# OpenBook.net
KiCad netlist of a schematic drawn in EAGLE
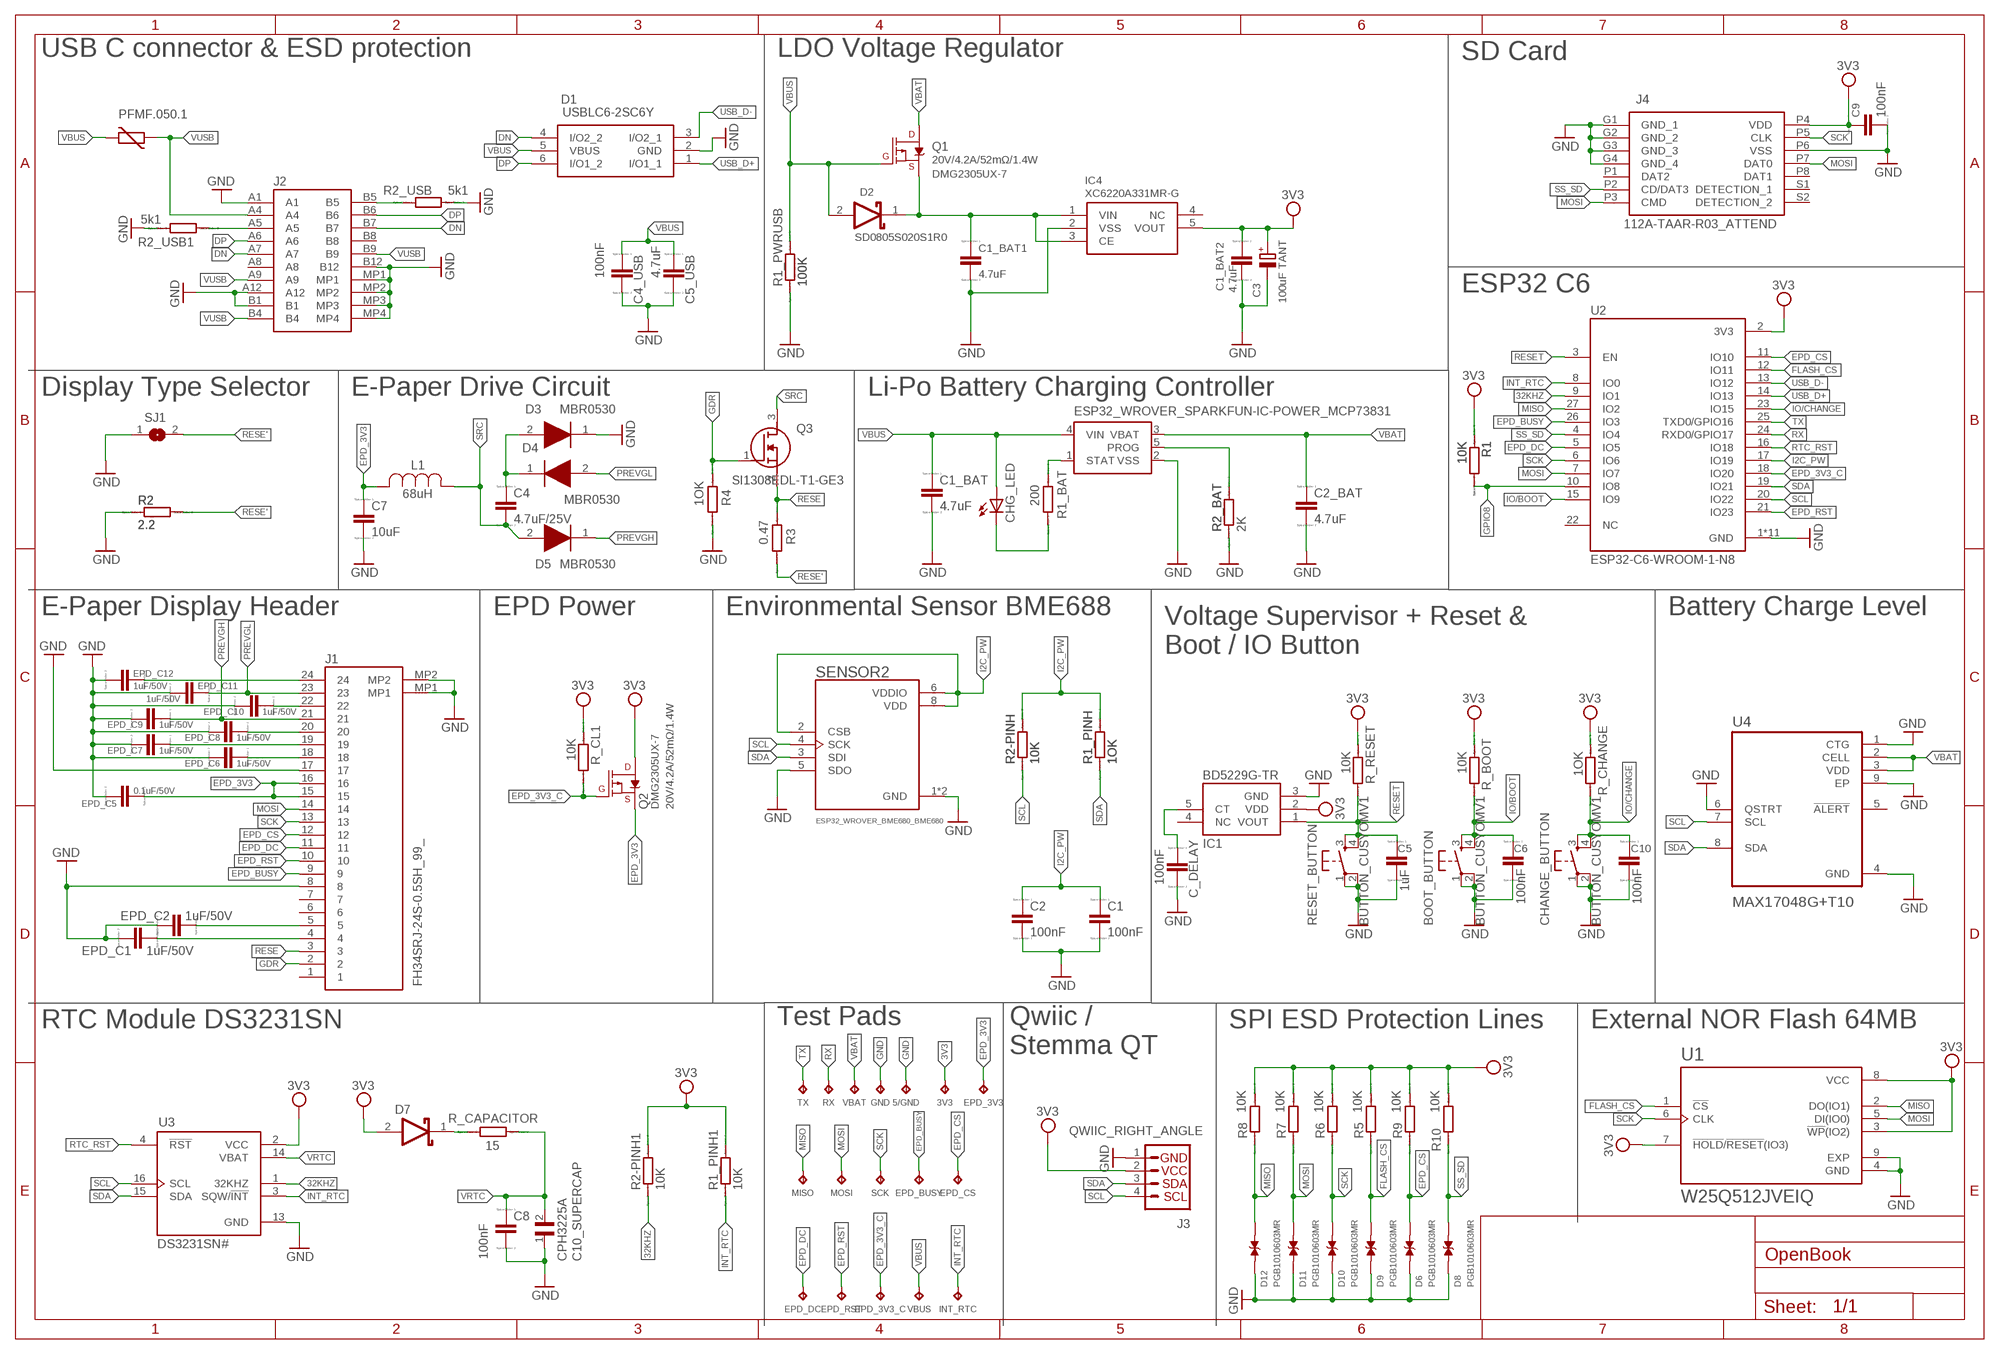
[diagram p0: schematic, sheet 1]

(export (version "E")
  (design (tool "Eeschema 10.0.6"))
  (components
    (comp (ref "3V3")
      (value "TPTP20R")
      (footprint "eagle-import:TP20R")
      (libsource (lib "eagle-import") (part "TPTP20R"))
    )
    (comp (ref "5/GND")
      (value "TPTP20R")
      (footprint "eagle-import:TP20R")
      (libsource (lib "eagle-import") (part "TPTP20R"))
    )
    (comp (ref "BOOT_BUTTON")
      (value "BUTTON_CUSYOMV1")
      (footprint "eagle-import:MYBUTTON")
      (libsource (lib "eagle-import") (part "BUTTON_CUSYOMV1"))
    )
    (comp (ref "C1")
      (value "100nF")
      (footprint "eagle-import:ESP32_WROVER_EAGLE-LTSPICE_C0402")
      (libsource (lib "eagle-import") (part "ESP32_WROVER_EAGLE-LTSPICE_CC0402"))
    )
    (comp (ref "C1_BAT")
      (value "4.7uF")
      (footprint "eagle-import:ESP32_WROVER_EAGLE-LTSPICE_C0402")
      (libsource (lib "eagle-import") (part "ESP32_WROVER_EAGLE-LTSPICE_CC0402"))
    )
    (comp (ref "C1_BAT1")
      (value "4.7uF")
      (footprint "eagle-import:ESP32_WROVER_EAGLE-LTSPICE_C0402")
      (libsource (lib "eagle-import") (part "ESP32_WROVER_EAGLE-LTSPICE_CC0402"))
    )
    (comp (ref "C1_BAT2")
      (value "4.7uF")
      (footprint "eagle-import:ESP32_WROVER_EAGLE-LTSPICE_C0402")
      (libsource (lib "eagle-import") (part "ESP32_WROVER_EAGLE-LTSPICE_CC0402"))
    )
    (comp (ref "C2")
      (value "100nF")
      (footprint "eagle-import:ESP32_WROVER_EAGLE-LTSPICE_C0402")
      (libsource (lib "eagle-import") (part "ESP32_WROVER_EAGLE-LTSPICE_CC0402"))
    )
    (comp (ref "C2_BAT")
      (value "4.7uF")
      (footprint "eagle-import:ESP32_WROVER_EAGLE-LTSPICE_C0402")
      (libsource (lib "eagle-import") (part "ESP32_WROVER_EAGLE-LTSPICE_CC0402"))
    )
    (comp (ref "C3")
      (value "100uF TANT")
      (footprint "eagle-import:RCL_CT3528")
      (libsource (lib "eagle-import") (part "RCL_CPOL-EUCT3528"))
    )
    (comp (ref "C4")
      (value "4.7uF/25V")
      (footprint "eagle-import:ESP32_WROVER_EAGLE-LTSPICE_C0402")
      (libsource (lib "eagle-import") (part "ESP32_WROVER_EAGLE-LTSPICE_CC0402"))
    )
    (comp (ref "C4_USB")
      (value "100nF")
      (footprint "eagle-import:ESP32_WROVER_EAGLE-LTSPICE_C0402")
      (libsource (lib "eagle-import") (part "ESP32_WROVER_EAGLE-LTSPICE_CC0402"))
    )
    (comp (ref "C5")
      (value "1uF")
      (footprint "eagle-import:ESP32_WROVER_EAGLE-LTSPICE_C0402")
      (libsource (lib "eagle-import") (part "ESP32_WROVER_EAGLE-LTSPICE_CC0402"))
    )
    (comp (ref "C5_USB")
      (value "4.7uF")
      (footprint "eagle-import:ESP32_WROVER_EAGLE-LTSPICE_C0402")
      (libsource (lib "eagle-import") (part "ESP32_WROVER_EAGLE-LTSPICE_CC0402"))
    )
    (comp (ref "C6")
      (value "100nF")
      (footprint "eagle-import:ESP32_WROVER_EAGLE-LTSPICE_C0402")
      (libsource (lib "eagle-import") (part "ESP32_WROVER_EAGLE-LTSPICE_CC0402"))
    )
    (comp (ref "C7")
      (value "10uF")
      (footprint "eagle-import:ESP32_WROVER_EAGLE-LTSPICE_C0402")
      (libsource (lib "eagle-import") (part "ESP32_WROVER_EAGLE-LTSPICE_CC0402"))
    )
    (comp (ref "C8")
      (value "100nF")
      (footprint "eagle-import:ESP32_WROVER_EAGLE-LTSPICE_C0402")
      (libsource (lib "eagle-import") (part "ESP32_WROVER_EAGLE-LTSPICE_CC0402"))
    )
    (comp (ref "C9")
      (value "100nF")
      (footprint "eagle-import:ESP32_WROVER_EAGLE-LTSPICE_C0402")
      (libsource (lib "eagle-import") (part "ESP32_WROVER_EAGLE-LTSPICE_CC0402"))
    )
    (comp (ref "C10")
      (value "100nF")
      (footprint "eagle-import:ESP32_WROVER_EAGLE-LTSPICE_C0402")
      (libsource (lib "eagle-import") (part "ESP32_WROVER_EAGLE-LTSPICE_CC0402"))
    )
    (comp (ref "C10_SUPERCAP")
      (value "CPH3225A")
      (footprint "eagle-import:CAPCP3225X100N")
      (fields (field (name "MF") "Seiko Instruments"))
      (libsource (lib "eagle-import") (part "CPH3225A"))
    )
    (comp (ref "CHANGE_BUTTON")
      (value "BUTTON_CUSYOMV1")
      (footprint "eagle-import:MYBUTTON")
      (libsource (lib "eagle-import") (part "BUTTON_CUSYOMV1"))
    )
    (comp (ref "CHG_LED")
      (value "ADAFRUIT_LEDCHIP-LED0603")
      (footprint "eagle-import:ADAFRUIT_CHIP-LED0603")
      (libsource (lib "eagle-import") (part "ADAFRUIT_LEDCHIP-LED0603"))
    )
    (comp (ref "C_DELAY")
      (value "100nF")
      (footprint "eagle-import:ESP32_WROVER_EAGLE-LTSPICE_C0402")
      (libsource (lib "eagle-import") (part "ESP32_WROVER_EAGLE-LTSPICE_CC0402"))
    )
    (comp (ref "D1")
      (value "USBLC6-2SC6Y")
      (footprint "eagle-import:SOT95P280X145-6N")
      (fields (field (name "MF") "STMicroelectronics"))
      (libsource (lib "eagle-import") (part "USBLC6-2SC6Y"))
    )
    (comp (ref "D2")
      (value "ESP32_WROVER_AVX---SD0805S020S1R0_AVX_SD0805S020S1R0_0_0AVX_SD0805S020S1R0_0_0")
      (footprint "eagle-import:ESP32_WROVER_AVX---SD0805S020S1R0_AVX_SD0805S020S1R0_0")
      (fields
        (field (name "DIGIKEY_PART_NUMBER") "478-7800-1-ND")
        (field (name "MF") "AVX")
        (field (name "MOUSER_PART_NUMBER") "581-SD0805S020S1R0")
      )
      (libsource (lib "eagle-import") (part "ESP32_WROVER_AVX---SD0805S020S1R0_AVX_SD0805S020S1R0_0_0AVX_SD0805S020S1R0_0_0"))
    )
    (comp (ref "D3")
      (value "MBR0530")
      (footprint "eagle-import:SOD3716X135N")
      (fields (field (name "MF") "ON Semiconductor"))
      (libsource (lib "eagle-import") (part "MBR0530"))
    )
    (comp (ref "D4")
      (value "MBR0530")
      (footprint "eagle-import:SOD3716X135N")
      (fields (field (name "MF") "ON Semiconductor"))
      (libsource (lib "eagle-import") (part "MBR0530"))
    )
    (comp (ref "D5")
      (value "MBR0530")
      (footprint "eagle-import:SOD3716X135N")
      (fields (field (name "MF") "ON Semiconductor"))
      (libsource (lib "eagle-import") (part "MBR0530"))
    )
    (comp (ref "D6")
      (value "PGB1010603MR")
      (footprint "eagle-import:DIOC1608X36N")
      (fields (field (name "MF") "Littelfuse Inc."))
      (libsource (lib "eagle-import") (part "PGB1010603MR"))
    )
    (comp (ref "D7")
      (value "ESP32_WROVER_AVX---SD0805S020S1R0_AVX_SD0805S020S1R0_0_0AVX_SD0805S020S1R0_0_0")
      (footprint "eagle-import:ESP32_WROVER_AVX---SD0805S020S1R0_AVX_SD0805S020S1R0_0")
      (fields
        (field (name "DIGIKEY_PART_NUMBER") "478-7800-1-ND")
        (field (name "MF") "AVX")
        (field (name "MOUSER_PART_NUMBER") "581-SD0805S020S1R0")
      )
      (libsource (lib "eagle-import") (part "ESP32_WROVER_AVX---SD0805S020S1R0_AVX_SD0805S020S1R0_0_0AVX_SD0805S020S1R0_0_0"))
    )
    (comp (ref "D8")
      (value "PGB1010603MR")
      (footprint "eagle-import:DIOC1608X36N")
      (fields (field (name "MF") "Littelfuse Inc."))
      (libsource (lib "eagle-import") (part "PGB1010603MR"))
    )
    (comp (ref "D9")
      (value "PGB1010603MR")
      (footprint "eagle-import:DIOC1608X36N")
      (fields (field (name "MF") "Littelfuse Inc."))
      (libsource (lib "eagle-import") (part "PGB1010603MR"))
    )
    (comp (ref "D10")
      (value "PGB1010603MR")
      (footprint "eagle-import:DIOC1608X36N")
      (fields (field (name "MF") "Littelfuse Inc."))
      (libsource (lib "eagle-import") (part "PGB1010603MR"))
    )
    (comp (ref "D11")
      (value "PGB1010603MR")
      (footprint "eagle-import:DIOC1608X36N")
      (fields (field (name "MF") "Littelfuse Inc."))
      (libsource (lib "eagle-import") (part "PGB1010603MR"))
    )
    (comp (ref "D12")
      (value "PGB1010603MR")
      (footprint "eagle-import:DIOC1608X36N")
      (fields (field (name "MF") "Littelfuse Inc."))
      (libsource (lib "eagle-import") (part "PGB1010603MR"))
    )
    (comp (ref "EPD_3V3")
      (value "TPTP20R")
      (footprint "eagle-import:TP20R")
      (libsource (lib "eagle-import") (part "TPTP20R"))
    )
    (comp (ref "EPD_3V3_C")
      (value "TPTP20R")
      (footprint "eagle-import:TP20R")
      (libsource (lib "eagle-import") (part "TPTP20R"))
    )
    (comp (ref "EPD_BUSY")
      (value "TPTP20R")
      (footprint "eagle-import:TP20R")
      (libsource (lib "eagle-import") (part "TPTP20R"))
    )
    (comp (ref "EPD_C1")
      (value "1uF/50V")
      (footprint "eagle-import:ESP32_WROVER_EAGLE-LTSPICE_C0402")
      (libsource (lib "eagle-import") (part "ESP32_WROVER_EAGLE-LTSPICE_CC0402"))
    )
    (comp (ref "EPD_C2")
      (value "1uF/50V")
      (footprint "eagle-import:ESP32_WROVER_EAGLE-LTSPICE_C0402")
      (libsource (lib "eagle-import") (part "ESP32_WROVER_EAGLE-LTSPICE_CC0402"))
    )
    (comp (ref "EPD_C5")
      (value "0.1uF/50V")
      (footprint "eagle-import:ESP32_WROVER_EAGLE-LTSPICE_C0402")
      (libsource (lib "eagle-import") (part "ESP32_WROVER_EAGLE-LTSPICE_CC0402"))
    )
    (comp (ref "EPD_C6")
      (value "1uF/50V")
      (footprint "eagle-import:ESP32_WROVER_EAGLE-LTSPICE_C0402")
      (libsource (lib "eagle-import") (part "ESP32_WROVER_EAGLE-LTSPICE_CC0402"))
    )
    (comp (ref "EPD_C7")
      (value "1uF/50V")
      (footprint "eagle-import:ESP32_WROVER_EAGLE-LTSPICE_C0402")
      (libsource (lib "eagle-import") (part "ESP32_WROVER_EAGLE-LTSPICE_CC0402"))
    )
    (comp (ref "EPD_C8")
      (value "1uF/50V")
      (footprint "eagle-import:ESP32_WROVER_EAGLE-LTSPICE_C0402")
      (libsource (lib "eagle-import") (part "ESP32_WROVER_EAGLE-LTSPICE_CC0402"))
    )
    (comp (ref "EPD_C9")
      (value "1uF/50V")
      (footprint "eagle-import:ESP32_WROVER_EAGLE-LTSPICE_C0402")
      (libsource (lib "eagle-import") (part "ESP32_WROVER_EAGLE-LTSPICE_CC0402"))
    )
    (comp (ref "EPD_C10")
      (value "1uF/50V")
      (footprint "eagle-import:ESP32_WROVER_EAGLE-LTSPICE_C0402")
      (libsource (lib "eagle-import") (part "ESP32_WROVER_EAGLE-LTSPICE_CC0402"))
    )
    (comp (ref "EPD_C11")
      (value "1uF/50V")
      (footprint "eagle-import:ESP32_WROVER_EAGLE-LTSPICE_C0402")
      (libsource (lib "eagle-import") (part "ESP32_WROVER_EAGLE-LTSPICE_CC0402"))
    )
    (comp (ref "EPD_C12")
      (value "1uF/50V")
      (footprint "eagle-import:ESP32_WROVER_EAGLE-LTSPICE_C0402")
      (libsource (lib "eagle-import") (part "ESP32_WROVER_EAGLE-LTSPICE_CC0402"))
    )
    (comp (ref "EPD_CS")
      (value "TPTP20R")
      (footprint "eagle-import:TP20R")
      (libsource (lib "eagle-import") (part "TPTP20R"))
    )
    (comp (ref "EPD_DC")
      (value "TPTP20R")
      (footprint "eagle-import:TP20R")
      (libsource (lib "eagle-import") (part "TPTP20R"))
    )
    (comp (ref "EPD_RST")
      (value "TPTP20R")
      (footprint "eagle-import:TP20R")
      (libsource (lib "eagle-import") (part "TPTP20R"))
    )
    (comp (ref "GND")
      (value "TPTP20R")
      (footprint "eagle-import:TP20R")
      (libsource (lib "eagle-import") (part "TPTP20R"))
    )
    (comp (ref "IC1")
      (value "BD5229G-TR")
      (footprint "eagle-import:SOT95P280X125-5N")
      (fields (field (name "MOUSER_PART_NUMBER") "755-BD5229G-TR"))
      (libsource (lib "eagle-import") (part "BD5229G-TR"))
    )
    (comp (ref "IC4")
      (value "XC6220A331MR-G")
      (footprint "eagle-import:SOT95P280X120-5N")
      (fields (field (name "MOUSER_PART_NUMBER") "865-XC6220A331MR-G"))
      (libsource (lib "eagle-import") (part "XC6220A331MR-G"))
    )
    (comp (ref "INT_RTC")
      (value "TPTP20R")
      (footprint "eagle-import:TP20R")
      (libsource (lib "eagle-import") (part "TPTP20R"))
    )
    (comp (ref "J1")
      (value "FH34SRJ-24S-0.5SH_99_")
      (footprint "eagle-import:FH34SRJ24S05SH99")
      (fields
        (field (name "MANUFACTURER_PART_NUMBER") "FH34SRJ-24S-0.5SH(99)")
        (field (name "MOUSER_PART_NUMBER") "798-FH34SRJ24S05SH99")
      )
      (libsource (lib "eagle-import") (part "FH34SRJ-24S-0.5SH_99_"))
    )
    (comp (ref "J2")
      (value "SAMACSYS_PARTS_USB4110-GF-A")
      (footprint "eagle-import:SAMACSYS_PARTS_USB4110GFA")
      (fields
        (field (name "MANUFACTURER_PART_NUMBER") "USB4110-GF-A")
        (field (name "MOUSER_PART_NUMBER") "640-USB4110-GF-A")
      )
      (libsource (lib "eagle-import") (part "SAMACSYS_PARTS_USB4110-GF-A"))
    )
    (comp (ref "J3")
      (value "QWIIC_RIGHT_ANGLE")
      (footprint "eagle-import:JST04_1MM_RA")
      (libsource (lib "eagle-import") (part "QWIIC_CONNECTORJS-1MM"))
    )
    (comp (ref "J4")
      (value "112A-TAAR-R03_ATTEND")
      (footprint "eagle-import:112ATAARR03ATTEND")
      (fields (field (name "MANUFACTURER_PART_NUMBER") "112A-TAAR-R03 ATTEND"))
      (libsource (lib "eagle-import") (part "112A-TAAR-R03_ATTEND"))
    )
    (comp (ref "L1")
      (value "744043680IND_4828-WE-TPC_WRE")
      (footprint "eagle-import:IND_4828-WE-TPC_WRE")
      (fields
        (field (name "MANUFACTURER_PART_NUMBER") "744043680")
        (field (name "COPYRIGHT") "Copyright (C) 2024 Ultra Librarian. All rights reserved.")
      )
      (libsource (lib "eagle-import") (part "744043680IND_4828-WE-TPC_WRE"))
    )
    (comp (ref "MISO")
      (value "TPTP20R")
      (footprint "eagle-import:TP20R")
      (libsource (lib "eagle-import") (part "TPTP20R"))
    )
    (comp (ref "MOSI")
      (value "TPTP20R")
      (footprint "eagle-import:TP20R")
      (libsource (lib "eagle-import") (part "TPTP20R"))
    )
    (comp (ref "PFMF.050.1")
      (value "ESP32C6_VARISTORCN1812")
      (footprint "eagle-import:ESP32C6_VARISTOR_CT_CN1812")
      (libsource (lib "eagle-import") (part "ESP32C6_VARISTORCN1812"))
    )
    (comp (ref "Q1")
      (value "20V/4.2A/52mΩ/1.4W")
      (footprint "eagle-import:ESP32_WROVER_SPARKFUN-DISCRETESEMI_SOT23-3")
      (libsource (lib "eagle-import") (part "ESP32_WROVER_SPARKFUN-DISCRETESEMI_MOSFET_PCH-DMG2305UX-7"))
    )
    (comp (ref "Q2")
      (value "20V/4.2A/52mΩ/1.4W")
      (footprint "eagle-import:ESP32_WROVER_SPARKFUN-DISCRETESEMI_SOT23-3")
      (libsource (lib "eagle-import") (part "ESP32_WROVER_SPARKFUN-DISCRETESEMI_MOSFET_PCH-DMG2305UX-7"))
    )
    (comp (ref "Q3")
      (value "SI1308EDL-T1-GE3")
      (footprint "eagle-import:SOT65P210X110-3N")
      (fields (field (name "MF") "Vishay Siliconix"))
      (libsource (lib "eagle-import") (part "SI1308EDL-T1-GE3"))
    )
    (comp (ref "R1")
      (value "10K")
      (footprint "eagle-import:ESP32_WROVER_EAGLE-LTSPICE_R0402")
      (libsource (lib "eagle-import") (part "ESP32_WROVER_EAGLE-LTSPICE_RR0402"))
    )
    (comp (ref "R1_BAT")
      (value "200")
      (footprint "eagle-import:ESP32_WROVER_EAGLE-LTSPICE_R0402")
      (libsource (lib "eagle-import") (part "ESP32_WROVER_EAGLE-LTSPICE_RR0402"))
    )
    (comp (ref "R1_PINH")
      (value "1OK")
      (footprint "eagle-import:ESP32_WROVER_EAGLE-LTSPICE_R0402")
      (libsource (lib "eagle-import") (part "ESP32_WROVER_EAGLE-LTSPICE_RR0402"))
    )
    (comp (ref "R1_PINH1")
      (value "10K")
      (footprint "eagle-import:ESP32_WROVER_EAGLE-LTSPICE_R0402")
      (libsource (lib "eagle-import") (part "ESP32_WROVER_EAGLE-LTSPICE_RR0402"))
    )
    (comp (ref "R1_PWRUSB")
      (value "100K")
      (footprint "eagle-import:ESP32_WROVER_EAGLE-LTSPICE_R0402")
      (libsource (lib "eagle-import") (part "ESP32_WROVER_EAGLE-LTSPICE_RR0402"))
    )
    (comp (ref "R2")
      (value "2.2")
      (footprint "eagle-import:ESP32_WROVER_EAGLE-LTSPICE_R0402")
      (libsource (lib "eagle-import") (part "ESP32_WROVER_EAGLE-LTSPICE_RR0402"))
    )
    (comp (ref "R2-PINH")
      (value "10K")
      (footprint "eagle-import:ESP32_WROVER_EAGLE-LTSPICE_R0402")
      (libsource (lib "eagle-import") (part "ESP32_WROVER_EAGLE-LTSPICE_RR0402"))
    )
    (comp (ref "R2-PINH1")
      (value "10K")
      (footprint "eagle-import:ESP32_WROVER_EAGLE-LTSPICE_R0402")
      (libsource (lib "eagle-import") (part "ESP32_WROVER_EAGLE-LTSPICE_RR0402"))
    )
    (comp (ref "R2_BAT")
      (value "2K")
      (footprint "eagle-import:ESP32_WROVER_EAGLE-LTSPICE_R0402")
      (libsource (lib "eagle-import") (part "ESP32_WROVER_EAGLE-LTSPICE_RR0402"))
    )
    (comp (ref "R2_USB")
      (value "5k1")
      (footprint "eagle-import:ESP32_WROVER_EAGLE-LTSPICE_R0402")
      (libsource (lib "eagle-import") (part "ESP32_WROVER_EAGLE-LTSPICE_RR0402"))
    )
    (comp (ref "R2_USB1")
      (value "5k1")
      (footprint "eagle-import:ESP32_WROVER_EAGLE-LTSPICE_R0402")
      (libsource (lib "eagle-import") (part "ESP32_WROVER_EAGLE-LTSPICE_RR0402"))
    )
    (comp (ref "R3")
      (value "0.47")
      (footprint "eagle-import:ESP32_WROVER_EAGLE-LTSPICE_R0402")
      (libsource (lib "eagle-import") (part "ESP32_WROVER_EAGLE-LTSPICE_RR0402"))
    )
    (comp (ref "R4")
      (value "1OK")
      (footprint "eagle-import:ESP32_WROVER_EAGLE-LTSPICE_R0402")
      (libsource (lib "eagle-import") (part "ESP32_WROVER_EAGLE-LTSPICE_RR0402"))
    )
    (comp (ref "R5")
      (value "10K")
      (footprint "eagle-import:ESP32_WROVER_EAGLE-LTSPICE_R0402")
      (libsource (lib "eagle-import") (part "ESP32_WROVER_EAGLE-LTSPICE_RR0402"))
    )
    (comp (ref "R6")
      (value "10K")
      (footprint "eagle-import:ESP32_WROVER_EAGLE-LTSPICE_R0402")
      (libsource (lib "eagle-import") (part "ESP32_WROVER_EAGLE-LTSPICE_RR0402"))
    )
    (comp (ref "R7")
      (value "10K")
      (footprint "eagle-import:ESP32_WROVER_EAGLE-LTSPICE_R0402")
      (libsource (lib "eagle-import") (part "ESP32_WROVER_EAGLE-LTSPICE_RR0402"))
    )
    (comp (ref "R8")
      (value "10K")
      (footprint "eagle-import:ESP32_WROVER_EAGLE-LTSPICE_R0402")
      (libsource (lib "eagle-import") (part "ESP32_WROVER_EAGLE-LTSPICE_RR0402"))
    )
    (comp (ref "R9")
      (value "10K")
      (footprint "eagle-import:ESP32_WROVER_EAGLE-LTSPICE_R0402")
      (libsource (lib "eagle-import") (part "ESP32_WROVER_EAGLE-LTSPICE_RR0402"))
    )
    (comp (ref "R10")
      (value "10K")
      (footprint "eagle-import:ESP32_WROVER_EAGLE-LTSPICE_R0402")
      (libsource (lib "eagle-import") (part "ESP32_WROVER_EAGLE-LTSPICE_RR0402"))
    )
    (comp (ref "RESET_BUTTON")
      (value "BUTTON_CUSYOMV1")
      (footprint "eagle-import:MYBUTTON")
      (libsource (lib "eagle-import") (part "BUTTON_CUSYOMV1"))
    )
    (comp (ref "RX")
      (value "TPTP20R")
      (footprint "eagle-import:TP20R")
      (libsource (lib "eagle-import") (part "TPTP20R"))
    )
    (comp (ref "R_BOOT")
      (value "10K")
      (footprint "eagle-import:ESP32_WROVER_EAGLE-LTSPICE_R0402")
      (libsource (lib "eagle-import") (part "ESP32_WROVER_EAGLE-LTSPICE_RR0402"))
    )
    (comp (ref "R_CAPACITOR")
      (value "15")
      (footprint "eagle-import:ESP32_WROVER_EAGLE-LTSPICE_R0402")
      (libsource (lib "eagle-import") (part "ESP32_WROVER_EAGLE-LTSPICE_RR0402"))
    )
    (comp (ref "R_CHANGE")
      (value "1OK")
      (footprint "eagle-import:ESP32_WROVER_EAGLE-LTSPICE_R0402")
      (libsource (lib "eagle-import") (part "ESP32_WROVER_EAGLE-LTSPICE_RR0402"))
    )
    (comp (ref "R_CL1")
      (value "10K")
      (footprint "eagle-import:ESP32_WROVER_EAGLE-LTSPICE_R0402")
      (libsource (lib "eagle-import") (part "ESP32_WROVER_EAGLE-LTSPICE_RR0402"))
    )
    (comp (ref "R_RESET")
      (value "10K")
      (footprint "eagle-import:ESP32_WROVER_EAGLE-LTSPICE_R0402")
      (libsource (lib "eagle-import") (part "ESP32_WROVER_EAGLE-LTSPICE_RR0402"))
    )
    (comp (ref "SCK")
      (value "TPTP20R")
      (footprint "eagle-import:TP20R")
      (libsource (lib "eagle-import") (part "TPTP20R"))
    )
    (comp (ref "SENSOR2")
      (value "ESP32_WROVER_BME680_BME680")
      (footprint "eagle-import:ESP32_WROVER_BME680_PSON80P300X300X100-8N")
      (fields (field (name "MF") "Bosch Sensortec") (field (name "MP") "BME680"))
      (libsource (lib "eagle-import") (part "ESP32_WROVER_BME680_BME680"))
    )
    (comp (ref "SJ1") (value "SJ") (footprint "eagle-import:SJ") (libsource (lib "eagle-import") (part "SJ")))
    (comp (ref "TX")
      (value "TPTP20R")
      (footprint "eagle-import:TP20R")
      (libsource (lib "eagle-import") (part "TPTP20R"))
    )
    (comp (ref "U0")
      (value "ESP32_WROVER_SPARKFUN-IC-POWER_MCP73831")
      (footprint "eagle-import:ESP32_WROVER_SPARKFUN-IC-POWER_SOT23-5")
      (libsource (lib "eagle-import") (part "ESP32_WROVER_SPARKFUN-IC-POWER_MCP73831"))
    )
    (comp (ref "U1")
      (value "W25Q512JVEIQ")
      (footprint "eagle-import:SON127P600X800X80-9N")
      (fields (field (name "MF") "Winbond Electronics"))
      (libsource (lib "eagle-import") (part "W25Q512JVEIQ"))
    )
    (comp (ref "U2")
      (value "ESP32-C6-WROOM-1-N8")
      (footprint "eagle-import:XCVR_ESP32-C6-WROOM-1-N8")
      (fields (field (name "MF") "Espressif Systems"))
      (libsource (lib "eagle-import") (part "ESP32-C6-WROOM-1-N8"))
    )
    (comp (ref "U3")
      (value "DS3231SN#")
      (footprint "eagle-import:SOIC127P1032X265-16N")
      (fields (field (name "MF") "Analog Devices"))
      (libsource (lib "eagle-import") (part "DS3231SN#"))
    )
    (comp (ref "U4")
      (value "MAX17048G+T10")
      (footprint "eagle-import:SON50P200X200X80-9N")
      (fields (field (name "MF") "Analog Devices"))
      (libsource (lib "eagle-import") (part "MAX17048G+T10"))
    )
    (comp (ref "VBAT")
      (value "TPTP20R")
      (footprint "eagle-import:TP20R")
      (libsource (lib "eagle-import") (part "TPTP20R"))
    )
    (comp (ref "VBUS")
      (value "TPTP20R")
      (footprint "eagle-import:TP20R")
      (libsource (lib "eagle-import") (part "TPTP20R"))
    )
  )
  (nets
    (net (code "1") (name "3V3") (class "Default")
      (node (ref "3V3") (pin "TP") (pinfunction "TP_TP") (pintype "input"))
      (node (ref "C1_BAT2") (pin "1") (pinfunction "1_1") (pintype "passive"))
      (node (ref "C3") (pin "+") (pinfunction "+_+") (pintype "passive"))
      (node (ref "C9") (pin "1") (pinfunction "1_1") (pintype "passive"))
      (node (ref "D7") (pin "2") (pinfunction "ANODE_2") (pintype "bidirectional"))
      (node (ref "IC1") (pin "2") (pinfunction "VDD_2") (pintype "bidirectional"))
      (node (ref "IC4") (pin "5") (pinfunction "VOUT_5") (pintype "bidirectional"))
      (node (ref "J3") (pin "2") (pinfunction "2_2") (pintype "power_in"))
      (node (ref "J4") (pin "P4") (pinfunction "VDD_P4") (pintype "bidirectional"))
      (node (ref "Q2") (pin "3") (pinfunction "D_3") (pintype "bidirectional"))
      (node (ref "R1") (pin "1") (pinfunction "1_1") (pintype "passive"))
      (node (ref "R10") (pin "2") (pinfunction "2_2") (pintype "passive"))
      (node (ref "R1_PINH1") (pin "2") (pinfunction "2_2") (pintype "passive"))
      (node (ref "R2-PINH1") (pin "2") (pinfunction "2_2") (pintype "passive"))
      (node (ref "R5") (pin "2") (pinfunction "2_2") (pintype "passive"))
      (node (ref "R6") (pin "2") (pinfunction "2_2") (pintype "passive"))
      (node (ref "R7") (pin "2") (pinfunction "2_2") (pintype "passive"))
      (node (ref "R8") (pin "2") (pinfunction "2_2") (pintype "passive"))
      (node (ref "R9") (pin "2") (pinfunction "2_2") (pintype "passive"))
      (node (ref "R_BOOT") (pin "1") (pinfunction "1_1") (pintype "passive"))
      (node (ref "R_CHANGE") (pin "1") (pinfunction "1_1") (pintype "passive"))
      (node (ref "R_CL1") (pin "1") (pinfunction "1_1") (pintype "passive"))
      (node (ref "R_RESET") (pin "1") (pinfunction "1_1") (pintype "passive"))
      (node (ref "U1") (pin "3") (pinfunction "~{WP}(IO2)_3") (pintype "bidirectional"))
      (node (ref "U1") (pin "7") (pinfunction "~{HOLD}/~{RESET}(IO3)_7") (pintype "bidirectional"))
      (node (ref "U1") (pin "8") (pinfunction "VCC_8") (pintype "power_in"))
      (node (ref "U2") (pin "2") (pinfunction "3V3_2") (pintype "power_in"))
      (node (ref "U3") (pin "2") (pinfunction "VCC_2") (pintype "power_in"))
    )
    (net (code "2") (name "32KHZ") (class "Default")
      (node (ref "R2-PINH1") (pin "1") (pinfunction "1_1") (pintype "passive"))
      (node (ref "U2") (pin "9") (pinfunction "IO1_9") (pintype "bidirectional"))
      (node (ref "U3") (pin "1") (pinfunction "32KHZ_1") (pintype "output"))
    )
    (net (code "3") (name "DN") (class "Default")
      (node (ref "D1") (pin "4") (pinfunction "I/O2_2_4") (pintype "bidirectional"))
      (node (ref "J2") (pin "A7") (pinfunction "A7_A7") (pintype "bidirectional"))
      (node (ref "J2") (pin "B7") (pinfunction "B7_B7") (pintype "bidirectional"))
    )
    (net (code "4") (name "DP") (class "Default")
      (node (ref "D1") (pin "6") (pinfunction "I/O1_2_6") (pintype "bidirectional"))
      (node (ref "J2") (pin "A6") (pinfunction "A6_A6") (pintype "bidirectional"))
      (node (ref "J2") (pin "B6") (pinfunction "B6_B6") (pintype "bidirectional"))
    )
    (net (code "5") (name "EPD_3V3") (class "Default")
      (node (ref "C7") (pin "1") (pinfunction "1_1") (pintype "passive"))
      (node (ref "EPD_3V3") (pin "TP") (pinfunction "TP_TP") (pintype "input"))
      (node (ref "EPD_C5") (pin "1") (pinfunction "1_1") (pintype "passive"))
      (node (ref "J1") (pin "15") (pinfunction "15_15") (pintype "bidirectional"))
      (node (ref "J1") (pin "16") (pinfunction "16_16") (pintype "bidirectional"))
      (node (ref "L1") (pin "2") (pinfunction "2_2") (pintype "passive"))
      (node (ref "Q2") (pin "2") (pinfunction "S_2") (pintype "bidirectional"))
    )
    (net (code "6") (name "EPD_3V3_C") (class "Default")
      (node (ref "EPD_3V3_C") (pin "TP") (pinfunction "TP_TP") (pintype "input"))
      (node (ref "Q2") (pin "1") (pinfunction "G_1") (pintype "bidirectional"))
      (node (ref "R_CL1") (pin "2") (pinfunction "2_2") (pintype "passive"))
      (node (ref "U2") (pin "18") (pinfunction "IO20_18") (pintype "bidirectional"))
    )
    (net (code "7") (name "EPD_BUSY") (class "Default")
      (node (ref "EPD_BUSY") (pin "TP") (pinfunction "TP_TP") (pintype "input"))
      (node (ref "J1") (pin "9") (pinfunction "9_9") (pintype "bidirectional"))
      (node (ref "U2") (pin "26") (pinfunction "IO3_26") (pintype "bidirectional"))
    )
    (net (code "8") (name "EPD_CS") (class "Default")
      (node (ref "D6") (pin "2") (pinfunction "2_2") (pintype "passive"))
      (node (ref "EPD_CS") (pin "TP") (pinfunction "TP_TP") (pintype "input"))
      (node (ref "J1") (pin "12") (pinfunction "12_12") (pintype "bidirectional"))
      (node (ref "R9") (pin "1") (pinfunction "1_1") (pintype "passive"))
      (node (ref "U2") (pin "11") (pinfunction "IO10_11") (pintype "bidirectional"))
    )
    (net (code "9") (name "EPD_DC") (class "Default")
      (node (ref "EPD_DC") (pin "TP") (pinfunction "TP_TP") (pintype "input"))
      (node (ref "J1") (pin "11") (pinfunction "11_11") (pintype "bidirectional"))
      (node (ref "U2") (pin "5") (pinfunction "IO5_5") (pintype "bidirectional"))
    )
    (net (code "10") (name "EPD_RST") (class "Default")
      (node (ref "EPD_RST") (pin "TP") (pinfunction "TP_TP") (pintype "input"))
      (node (ref "J1") (pin "10") (pinfunction "10_10") (pintype "bidirectional"))
      (node (ref "U2") (pin "21") (pinfunction "IO23_21") (pintype "bidirectional"))
    )
    (net (code "11") (name "FLASH_CS") (class "Default")
      (node (ref "D9") (pin "2") (pinfunction "2_2") (pintype "passive"))
      (node (ref "R5") (pin "1") (pinfunction "1_1") (pintype "passive"))
      (node (ref "U1") (pin "1") (pinfunction "~{CS}_1") (pintype "input"))
      (node (ref "U2") (pin "12") (pinfunction "IO11_12") (pintype "bidirectional"))
    )
    (net (code "12") (name "GDR") (class "Default")
      (node (ref "J1") (pin "2") (pinfunction "2_2") (pintype "bidirectional"))
      (node (ref "Q3") (pin "1") (pinfunction "G_1") (pintype "bidirectional"))
      (node (ref "R4") (pin "2") (pinfunction "2_2") (pintype "passive"))
    )
    (net (code "13") (name "GND") (class "Default")
      (node (ref "5/GND") (pin "TP") (pinfunction "TP_TP") (pintype "input"))
      (node (ref "BOOT_BUTTON") (pin "1") (pinfunction "1_1") (pintype "passive"))
      (node (ref "BOOT_BUTTON") (pin "2") (pinfunction "2_2") (pintype "passive"))
      (node (ref "C1") (pin "2") (pinfunction "2_2") (pintype "passive"))
      (node (ref "C10") (pin "2") (pinfunction "2_2") (pintype "passive"))
      (node (ref "C10_SUPERCAP") (pin "1") (pinfunction "1_1") (pintype "passive"))
      (node (ref "C1_BAT") (pin "2") (pinfunction "2_2") (pintype "passive"))
      (node (ref "C1_BAT1") (pin "2") (pinfunction "2_2") (pintype "passive"))
      (node (ref "C1_BAT2") (pin "2") (pinfunction "2_2") (pintype "passive"))
      (node (ref "C2") (pin "2") (pinfunction "2_2") (pintype "passive"))
      (node (ref "C2_BAT") (pin "2") (pinfunction "2_2") (pintype "passive"))
      (node (ref "C3") (pin "-") (pinfunction "-_-") (pintype "passive"))
      (node (ref "C4_USB") (pin "2") (pinfunction "2_2") (pintype "passive"))
      (node (ref "C5") (pin "2") (pinfunction "2_2") (pintype "passive"))
      (node (ref "C5_USB") (pin "2") (pinfunction "2_2") (pintype "passive"))
      (node (ref "C6") (pin "2") (pinfunction "2_2") (pintype "passive"))
      (node (ref "C7") (pin "2") (pinfunction "2_2") (pintype "passive"))
      (node (ref "C8") (pin "2") (pinfunction "2_2") (pintype "passive"))
      (node (ref "C9") (pin "2") (pinfunction "2_2") (pintype "passive"))
      (node (ref "CHANGE_BUTTON") (pin "1") (pinfunction "1_1") (pintype "passive"))
      (node (ref "CHANGE_BUTTON") (pin "2") (pinfunction "2_2") (pintype "passive"))
      (node (ref "C_DELAY") (pin "2") (pinfunction "2_2") (pintype "passive"))
      (node (ref "D1") (pin "2") (pinfunction "GND_2") (pintype "bidirectional"))
      (node (ref "D10") (pin "1") (pinfunction "1_1") (pintype "passive"))
      (node (ref "D11") (pin "1") (pinfunction "1_1") (pintype "passive"))
      (node (ref "D12") (pin "1") (pinfunction "1_1") (pintype "passive"))
      (node (ref "D4") (pin "1") (pinfunction "K_1") (pintype "bidirectional"))
      (node (ref "D6") (pin "1") (pinfunction "1_1") (pintype "passive"))
      (node (ref "D8") (pin "1") (pinfunction "1_1") (pintype "passive"))
      (node (ref "D9") (pin "1") (pinfunction "1_1") (pintype "passive"))
      (node (ref "EPD_C1") (pin "2") (pinfunction "2_2") (pintype "passive"))
      (node (ref "EPD_C10") (pin "2") (pinfunction "2_2") (pintype "passive"))
      (node (ref "EPD_C11") (pin "2") (pinfunction "2_2") (pintype "passive"))
      (node (ref "EPD_C12") (pin "2") (pinfunction "2_2") (pintype "passive"))
      (node (ref "EPD_C2") (pin "2") (pinfunction "2_2") (pintype "passive"))
      (node (ref "EPD_C5") (pin "2") (pinfunction "2_2") (pintype "passive"))
      (node (ref "EPD_C6") (pin "2") (pinfunction "2_2") (pintype "passive"))
      (node (ref "EPD_C7") (pin "2") (pinfunction "2_2") (pintype "passive"))
      (node (ref "EPD_C8") (pin "2") (pinfunction "2_2") (pintype "passive"))
      (node (ref "EPD_C9") (pin "2") (pinfunction "2_2") (pintype "passive"))
      (node (ref "GND") (pin "TP") (pinfunction "TP_TP") (pintype "input"))
      (node (ref "IC1") (pin "3") (pinfunction "GND_3") (pintype "bidirectional"))
      (node (ref "IC4") (pin "2") (pinfunction "VSS_2") (pintype "bidirectional"))
      (node (ref "J1") (pin "17") (pinfunction "17_17") (pintype "bidirectional"))
      (node (ref "J1") (pin "8") (pinfunction "8_8") (pintype "bidirectional"))
      (node (ref "J1") (pin "MP1") (pinfunction "MP1_MP1") (pintype "bidirectional"))
      (node (ref "J1") (pin "MP2") (pinfunction "MP2_MP2") (pintype "bidirectional"))
      (node (ref "J2") (pin "A1") (pinfunction "A1_A1") (pintype "bidirectional"))
      (node (ref "J2") (pin "A12") (pinfunction "A12_A12") (pintype "bidirectional"))
      (node (ref "J2") (pin "B1") (pinfunction "B1_B1") (pintype "bidirectional"))
      (node (ref "J2") (pin "B12") (pinfunction "B12_B12") (pintype "bidirectional"))
      (node (ref "J2") (pin "MP1") (pinfunction "MP1_MP1") (pintype "bidirectional"))
      (node (ref "J2") (pin "MP2") (pinfunction "MP2_MP2") (pintype "bidirectional"))
      (node (ref "J2") (pin "MP3") (pinfunction "MP3_MP3") (pintype "bidirectional"))
      (node (ref "J2") (pin "MP4") (pinfunction "MP4_MP4") (pintype "bidirectional"))
      (node (ref "J3") (pin "1") (pinfunction "1_1") (pintype "power_in"))
      (node (ref "J4") (pin "G1") (pinfunction "GND_1_G1") (pintype "bidirectional"))
      (node (ref "J4") (pin "G2") (pinfunction "GND_2_G2") (pintype "bidirectional"))
      (node (ref "J4") (pin "G3") (pinfunction "GND_3_G3") (pintype "bidirectional"))
      (node (ref "J4") (pin "G4") (pinfunction "GND_4_G4") (pintype "bidirectional"))
      (node (ref "J4") (pin "P6") (pinfunction "VSS_P6") (pintype "bidirectional"))
      (node (ref "R1_PWRUSB") (pin "1") (pinfunction "1_1") (pintype "passive"))
      (node (ref "R2") (pin "1") (pinfunction "1_1") (pintype "passive"))
      (node (ref "R2_BAT") (pin "1") (pinfunction "1_1") (pintype "passive"))
      (node (ref "R2_USB") (pin "2") (pinfunction "2_2") (pintype "passive"))
      (node (ref "R2_USB1") (pin "1") (pinfunction "1_1") (pintype "passive"))
      (node (ref "R4") (pin "1") (pinfunction "1_1") (pintype "passive"))
      (node (ref "RESET_BUTTON") (pin "1") (pinfunction "1_1") (pintype "passive"))
      (node (ref "RESET_BUTTON") (pin "2") (pinfunction "2_2") (pintype "passive"))
      (node (ref "SENSOR2") (pin "1") (pinfunction "GND_1") (pintype "power_in"))
      (node (ref "SENSOR2") (pin "5") (pinfunction "SDO_5") (pintype "bidirectional"))
      (node (ref "SENSOR2") (pin "7") (pinfunction "GND_7") (pintype "power_in"))
      (node (ref "SJ1") (pin "1") (pinfunction "1_1") (pintype "passive"))
      (node (ref "U0") (pin "2") (pinfunction "VSS_2") (pintype "power_in"))
      (node (ref "U1") (pin "4") (pinfunction "GND_4") (pintype "power_in"))
      (node (ref "U1") (pin "9") (pinfunction "EXP_9") (pintype "passive"))
      (node (ref "U2") (pin "1") (pinfunction "GND_1") (pintype "power_in"))
      (node (ref "U2") (pin "28") (pinfunction "GND_28") (pintype "power_in"))
      (node (ref "U2") (pin "29_1") (pinfunction "GND_29_1") (pintype "power_in"))
      (node (ref "U2") (pin "29_2") (pinfunction "GND_29_2") (pintype "power_in"))
      (node (ref "U2") (pin "29_3") (pinfunction "GND_29_3") (pintype "power_in"))
      (node (ref "U2") (pin "29_4") (pinfunction "GND_29_4") (pintype "power_in"))
      (node (ref "U2") (pin "29_5") (pinfunction "GND_29_5") (pintype "power_in"))
      (node (ref "U2") (pin "29_6") (pinfunction "GND_29_6") (pintype "power_in"))
      (node (ref "U2") (pin "29_7") (pinfunction "GND_29_7") (pintype "power_in"))
      (node (ref "U2") (pin "29_8") (pinfunction "GND_29_8") (pintype "power_in"))
      (node (ref "U2") (pin "29_9") (pinfunction "GND_29_9") (pintype "power_in"))
      (node (ref "U3") (pin "13") (pinfunction "GND_13") (pintype "power_in"))
      (node (ref "U4") (pin "1") (pinfunction "CTG_1") (pintype "power_in"))
      (node (ref "U4") (pin "4") (pinfunction "GND_4") (pintype "power_in"))
      (node (ref "U4") (pin "6") (pinfunction "QSTRT_6") (pintype "input"))
      (node (ref "U4") (pin "9") (pinfunction "EP_9") (pintype "power_in"))
    )
    (net (code "14") (name "GPIO8") (class "Default")
      (node (ref "R1") (pin "2") (pinfunction "2_2") (pintype "passive"))
      (node (ref "U2") (pin "10") (pinfunction "IO8_10") (pintype "bidirectional"))
    )
    (net (code "15") (name "I2C_PW") (class "Default")
      (node (ref "C1") (pin "1") (pinfunction "1_1") (pintype "passive"))
      (node (ref "C2") (pin "1") (pinfunction "1_1") (pintype "passive"))
      (node (ref "R1_PINH") (pin "2") (pinfunction "2_2") (pintype "passive"))
      (node (ref "R2-PINH") (pin "2") (pinfunction "2_2") (pintype "passive"))
      (node (ref "SENSOR2") (pin "2") (pinfunction "CSB_2") (pintype "input"))
      (node (ref "SENSOR2") (pin "6") (pinfunction "VDDIO_6") (pintype "power_in"))
      (node (ref "SENSOR2") (pin "8") (pinfunction "VDD_8") (pintype "power_in"))
      (node (ref "U2") (pin "17") (pinfunction "IO19_17") (pintype "bidirectional"))
    )
    (net (code "16") (name "INT_RTC") (class "Default")
      (node (ref "INT_RTC") (pin "TP") (pinfunction "TP_TP") (pintype "input"))
      (node (ref "R1_PINH1") (pin "1") (pinfunction "1_1") (pintype "passive"))
      (node (ref "U2") (pin "8") (pinfunction "IO0_8") (pintype "bidirectional"))
      (node (ref "U3") (pin "3") (pinfunction "SQW/~{INT}_3") (pintype "output"))
    )
    (net (code "17") (name "IO{slash}BOOT") (class "Default")
      (node (ref "BOOT_BUTTON") (pin "3") (pinfunction "3_3") (pintype "passive"))
      (node (ref "BOOT_BUTTON") (pin "4") (pinfunction "4_4") (pintype "passive"))
      (node (ref "C6") (pin "1") (pinfunction "1_1") (pintype "passive"))
      (node (ref "R_BOOT") (pin "2") (pinfunction "2_2") (pintype "passive"))
      (node (ref "U2") (pin "15") (pinfunction "IO9_15") (pintype "bidirectional"))
    )
    (net (code "18") (name "IO{slash}CHANGE") (class "Default")
      (node (ref "C10") (pin "1") (pinfunction "1_1") (pintype "passive"))
      (node (ref "CHANGE_BUTTON") (pin "3") (pinfunction "3_3") (pintype "passive"))
      (node (ref "CHANGE_BUTTON") (pin "4") (pinfunction "4_4") (pintype "passive"))
      (node (ref "R_CHANGE") (pin "2") (pinfunction "2_2") (pintype "passive"))
      (node (ref "U2") (pin "23") (pinfunction "IO15_23") (pintype "bidirectional"))
    )
    (net (code "19") (name "MISO") (class "Default")
      (node (ref "D12") (pin "2") (pinfunction "2_2") (pintype "passive"))
      (node (ref "MISO") (pin "TP") (pinfunction "TP_TP") (pintype "input"))
      (node (ref "R8") (pin "1") (pinfunction "1_1") (pintype "passive"))
      (node (ref "U1") (pin "2") (pinfunction "DO(IO1)_2") (pintype "bidirectional"))
      (node (ref "U2") (pin "27") (pinfunction "IO2_27") (pintype "bidirectional"))
    )
    (net (code "20") (name "MOSI") (class "Default")
      (node (ref "D11") (pin "2") (pinfunction "2_2") (pintype "passive"))
      (node (ref "J1") (pin "14") (pinfunction "14_14") (pintype "bidirectional"))
      (node (ref "J4") (pin "P3") (pinfunction "CMD_P3") (pintype "bidirectional"))
      (node (ref "J4") (pin "P7") (pinfunction "DAT0_P7") (pintype "bidirectional"))
      (node (ref "MOSI") (pin "TP") (pinfunction "TP_TP") (pintype "input"))
      (node (ref "R7") (pin "1") (pinfunction "1_1") (pintype "passive"))
      (node (ref "U1") (pin "5") (pinfunction "DI(IO0)_5") (pintype "bidirectional"))
      (node (ref "U2") (pin "7") (pinfunction "IO7_7") (pintype "bidirectional"))
    )
    (net (code "21") (name "Net-(CHG_LED-PadC)") (class "Default")
      (node (ref "CHG_LED") (pin "C") (pinfunction "C_C") (pintype "passive"))
      (node (ref "R1_BAT") (pin "1") (pinfunction "1_1") (pintype "passive"))
    )
    (net (code "22") (name "Net-(D2-CATHODE)") (class "Default")
      (node (ref "C1_BAT1") (pin "1") (pinfunction "1_1") (pintype "passive"))
      (node (ref "D2") (pin "1") (pinfunction "CATHODE_1") (pintype "bidirectional"))
      (node (ref "IC4") (pin "1") (pinfunction "VIN_1") (pintype "bidirectional"))
      (node (ref "IC4") (pin "3") (pinfunction "CE_3") (pintype "bidirectional"))
      (node (ref "Q1") (pin "2") (pinfunction "S_2") (pintype "bidirectional"))
    )
    (net (code "23") (name "Net-(D3-K)") (class "Default")
      (node (ref "C4") (pin "1") (pinfunction "1_1") (pintype "passive"))
      (node (ref "D3") (pin "1") (pinfunction "K_1") (pintype "bidirectional"))
      (node (ref "D4") (pin "2") (pinfunction "A_2") (pintype "bidirectional"))
    )
    (net (code "24") (name "Net-(D7-CATHODE)") (class "Default")
      (node (ref "D7") (pin "1") (pinfunction "CATHODE_1") (pintype "bidirectional"))
      (node (ref "R_CAPACITOR") (pin "2") (pinfunction "2_2") (pintype "passive"))
    )
    (net (code "25") (name "Net-(EPD_C1-Pad1)") (class "Default")
      (node (ref "EPD_C1") (pin "1") (pinfunction "1_1") (pintype "passive"))
      (node (ref "J1") (pin "4") (pinfunction "4_4") (pintype "bidirectional"))
    )
    (net (code "26") (name "Net-(EPD_C2-Pad1)") (class "Default")
      (node (ref "EPD_C2") (pin "1") (pinfunction "1_1") (pintype "passive"))
      (node (ref "J1") (pin "5") (pinfunction "5_5") (pintype "bidirectional"))
    )
    (net (code "27") (name "Net-(EPD_C6-Pad1)") (class "Default")
      (node (ref "EPD_C6") (pin "1") (pinfunction "1_1") (pintype "passive"))
      (node (ref "J1") (pin "18") (pinfunction "18_18") (pintype "bidirectional"))
    )
    (net (code "28") (name "Net-(EPD_C7-Pad1)") (class "Default")
      (node (ref "EPD_C7") (pin "1") (pinfunction "1_1") (pintype "passive"))
      (node (ref "J1") (pin "19") (pinfunction "19_19") (pintype "bidirectional"))
    )
    (net (code "29") (name "Net-(EPD_C8-Pad1)") (class "Default")
      (node (ref "EPD_C8") (pin "1") (pinfunction "1_1") (pintype "passive"))
      (node (ref "J1") (pin "20") (pinfunction "20_20") (pintype "bidirectional"))
    )
    (net (code "30") (name "Net-(EPD_C10-Pad1)") (class "Default")
      (node (ref "EPD_C10") (pin "1") (pinfunction "1_1") (pintype "passive"))
      (node (ref "J1") (pin "22") (pinfunction "22_22") (pintype "bidirectional"))
    )
    (net (code "31") (name "Net-(EPD_C12-Pad1)") (class "Default")
      (node (ref "EPD_C12") (pin "1") (pinfunction "1_1") (pintype "passive"))
      (node (ref "J1") (pin "24") (pinfunction "24_24") (pintype "bidirectional"))
    )
    (net (code "32") (name "Net-(IC1-CT)") (class "Default")
      (node (ref "C_DELAY") (pin "1") (pinfunction "1_1") (pintype "passive"))
      (node (ref "IC1") (pin "5") (pinfunction "CT_5") (pintype "bidirectional"))
    )
    (net (code "33") (name "Net-(J2-PadA5)") (class "Default")
      (node (ref "J2") (pin "A5") (pinfunction "A5_A5") (pintype "bidirectional"))
      (node (ref "R2_USB1") (pin "2") (pinfunction "2_2") (pintype "passive"))
    )
    (net (code "34") (name "Net-(J2-PadB5)") (class "Default")
      (node (ref "J2") (pin "B5") (pinfunction "B5_B5") (pintype "bidirectional"))
      (node (ref "R2_USB") (pin "1") (pinfunction "1_1") (pintype "passive"))
    )
    (net (code "35") (name "Net-(U0-PROG)") (class "Default")
      (node (ref "R2_BAT") (pin "2") (pinfunction "2_2") (pintype "passive"))
      (node (ref "U0") (pin "5") (pinfunction "PROG_5") (pintype "input"))
    )
    (net (code "36") (name "Net-(U0-STAT)") (class "Default")
      (node (ref "R1_BAT") (pin "2") (pinfunction "2_2") (pintype "passive"))
      (node (ref "U0") (pin "1") (pinfunction "STAT_1") (pintype "output"))
    )
    (net (code "37") (name "PREVGH") (class "Default")
      (node (ref "D5") (pin "1") (pinfunction "K_1") (pintype "bidirectional"))
      (node (ref "EPD_C9") (pin "1") (pinfunction "1_1") (pintype "passive"))
      (node (ref "J1") (pin "21") (pinfunction "21_21") (pintype "bidirectional"))
    )
    (net (code "38") (name "PREVGL") (class "Default")
      (node (ref "D3") (pin "2") (pinfunction "A_2") (pintype "bidirectional"))
      (node (ref "EPD_C11") (pin "1") (pinfunction "1_1") (pintype "passive"))
      (node (ref "J1") (pin "23") (pinfunction "23_23") (pintype "bidirectional"))
    )
    (net (code "39") (name "RESE") (class "Default")
      (node (ref "J1") (pin "3") (pinfunction "3_3") (pintype "bidirectional"))
      (node (ref "Q3") (pin "2") (pinfunction "S_2") (pintype "bidirectional"))
      (node (ref "R3") (pin "2") (pinfunction "2_2") (pintype "passive"))
    )
    (net (code "40") (name "RESE'") (class "Default")
      (node (ref "R2") (pin "2") (pinfunction "2_2") (pintype "passive"))
      (node (ref "R3") (pin "1") (pinfunction "1_1") (pintype "passive"))
      (node (ref "SJ1") (pin "2") (pinfunction "2_2") (pintype "passive"))
    )
    (net (code "41") (name "RESET") (class "Default")
      (node (ref "C5") (pin "1") (pinfunction "1_1") (pintype "passive"))
      (node (ref "IC1") (pin "1") (pinfunction "VOUT_1") (pintype "bidirectional"))
      (node (ref "RESET_BUTTON") (pin "3") (pinfunction "3_3") (pintype "passive"))
      (node (ref "RESET_BUTTON") (pin "4") (pinfunction "4_4") (pintype "passive"))
      (node (ref "R_RESET") (pin "2") (pinfunction "2_2") (pintype "passive"))
      (node (ref "U2") (pin "3") (pinfunction "EN_3") (pintype "input"))
    )
    (net (code "42") (name "RTC_RST") (class "Default")
      (node (ref "U2") (pin "16") (pinfunction "IO18_16") (pintype "bidirectional"))
      (node (ref "U3") (pin "4") (pinfunction "~{RST}_4") (pintype "input"))
    )
    (net (code "43") (name "RX") (class "Default")
      (node (ref "RX") (pin "TP") (pinfunction "TP_TP") (pintype "input"))
      (node (ref "U2") (pin "24") (pinfunction "RXD0/GPIO17_24") (pintype "bidirectional"))
    )
    (net (code "44") (name "SCK") (class "Default")
      (node (ref "D10") (pin "2") (pinfunction "2_2") (pintype "passive"))
      (node (ref "J1") (pin "13") (pinfunction "13_13") (pintype "bidirectional"))
      (node (ref "J4") (pin "P5") (pinfunction "CLK_P5") (pintype "bidirectional"))
      (node (ref "R6") (pin "1") (pinfunction "1_1") (pintype "passive"))
      (node (ref "SCK") (pin "TP") (pinfunction "TP_TP") (pintype "input"))
      (node (ref "U1") (pin "6") (pinfunction "CLK_6") (pintype "input"))
      (node (ref "U2") (pin "6") (pinfunction "IO6_6") (pintype "bidirectional"))
    )
    (net (code "45") (name "SCL") (class "Default")
      (node (ref "J3") (pin "4") (pinfunction "4_4") (pintype "passive"))
      (node (ref "R2-PINH") (pin "1") (pinfunction "1_1") (pintype "passive"))
      (node (ref "SENSOR2") (pin "4") (pinfunction "SCK_4") (pintype "input"))
      (node (ref "U2") (pin "20") (pinfunction "IO22_20") (pintype "bidirectional"))
      (node (ref "U3") (pin "16") (pinfunction "SCL_16") (pintype "input"))
      (node (ref "U4") (pin "7") (pinfunction "SCL_7") (pintype "input"))
    )
    (net (code "46") (name "SDA") (class "Default")
      (node (ref "J3") (pin "3") (pinfunction "3_3") (pintype "passive"))
      (node (ref "R1_PINH") (pin "1") (pinfunction "1_1") (pintype "passive"))
      (node (ref "SENSOR2") (pin "3") (pinfunction "SDI_3") (pintype "bidirectional"))
      (node (ref "U2") (pin "19") (pinfunction "IO21_19") (pintype "bidirectional"))
      (node (ref "U3") (pin "15") (pinfunction "SDA_15") (pintype "bidirectional"))
      (node (ref "U4") (pin "8") (pinfunction "SDA_8") (pintype "bidirectional"))
    )
    (net (code "47") (name "SRC") (class "Default")
      (node (ref "C4") (pin "2") (pinfunction "2_2") (pintype "passive"))
      (node (ref "D5") (pin "2") (pinfunction "A_2") (pintype "bidirectional"))
      (node (ref "L1") (pin "1") (pinfunction "1_1") (pintype "passive"))
      (node (ref "Q3") (pin "3") (pinfunction "D_3") (pintype "bidirectional"))
    )
    (net (code "48") (name "SS_SD") (class "Default")
      (node (ref "D8") (pin "2") (pinfunction "2_2") (pintype "passive"))
      (node (ref "J4") (pin "P2") (pinfunction "CD/DAT3_P2") (pintype "bidirectional"))
      (node (ref "R10") (pin "1") (pinfunction "1_1") (pintype "passive"))
      (node (ref "U2") (pin "4") (pinfunction "IO4_4") (pintype "bidirectional"))
    )
    (net (code "49") (name "TX") (class "Default")
      (node (ref "TX") (pin "TP") (pinfunction "TP_TP") (pintype "input"))
      (node (ref "U2") (pin "25") (pinfunction "TXD0/GPIO16_25") (pintype "bidirectional"))
    )
    (net (code "50") (name "USB_D+") (class "Default")
      (node (ref "D1") (pin "1") (pinfunction "I/O1_1_1") (pintype "bidirectional"))
      (node (ref "U2") (pin "14") (pinfunction "IO13_14") (pintype "bidirectional"))
    )
    (net (code "51") (name "USB_D-") (class "Default")
      (node (ref "D1") (pin "3") (pinfunction "I/O2_1_3") (pintype "bidirectional"))
      (node (ref "U2") (pin "13") (pinfunction "IO12_13") (pintype "bidirectional"))
    )
    (net (code "52") (name "VBAT") (class "Default")
      (node (ref "C2_BAT") (pin "1") (pinfunction "1_1") (pintype "passive"))
      (node (ref "Q1") (pin "3") (pinfunction "D_3") (pintype "bidirectional"))
      (node (ref "U0") (pin "3") (pinfunction "VBAT_3") (pintype "power_in"))
      (node (ref "U4") (pin "2") (pinfunction "CELL_2") (pintype "power_in"))
      (node (ref "U4") (pin "3") (pinfunction "VDD_3") (pintype "power_in"))
      (node (ref "VBAT") (pin "TP") (pinfunction "TP_TP") (pintype "input"))
    )
    (net (code "53") (name "VBUS") (class "Default")
      (node (ref "C1_BAT") (pin "1") (pinfunction "1_1") (pintype "passive"))
      (node (ref "C4_USB") (pin "1") (pinfunction "1_1") (pintype "passive"))
      (node (ref "C5_USB") (pin "1") (pinfunction "1_1") (pintype "passive"))
      (node (ref "CHG_LED") (pin "A") (pinfunction "A_A") (pintype "passive"))
      (node (ref "D1") (pin "5") (pinfunction "VBUS_5") (pintype "bidirectional"))
      (node (ref "D2") (pin "2") (pinfunction "ANODE_2") (pintype "bidirectional"))
      (node (ref "PFMF.050.1") (pin "2") (pinfunction "2_2") (pintype "passive"))
      (node (ref "Q1") (pin "1") (pinfunction "G_1") (pintype "bidirectional"))
      (node (ref "R1_PWRUSB") (pin "2") (pinfunction "2_2") (pintype "passive"))
      (node (ref "U0") (pin "4") (pinfunction "VIN_4") (pintype "power_in"))
      (node (ref "VBUS") (pin "TP") (pinfunction "TP_TP") (pintype "input"))
    )
    (net (code "54") (name "VRTC") (class "Default")
      (node (ref "C10_SUPERCAP") (pin "2") (pinfunction "2_2") (pintype "passive"))
      (node (ref "C8") (pin "1") (pinfunction "1_1") (pintype "passive"))
      (node (ref "R_CAPACITOR") (pin "1") (pinfunction "1_1") (pintype "passive"))
      (node (ref "U3") (pin "14") (pinfunction "VBAT_14") (pintype "power_in"))
    )
    (net (code "55") (name "VUSB") (class "Default")
      (node (ref "J2") (pin "A4") (pinfunction "A4_A4") (pintype "bidirectional"))
      (node (ref "J2") (pin "A9") (pinfunction "A9_A9") (pintype "bidirectional"))
      (node (ref "J2") (pin "B4") (pinfunction "B4_B4") (pintype "bidirectional"))
      (node (ref "J2") (pin "B9") (pinfunction "B9_B9") (pintype "bidirectional"))
      (node (ref "PFMF.050.1") (pin "1") (pinfunction "1_1") (pintype "passive"))
    )
    (net (code "56") (name "unconnected-(IC1-NC-Pad4)") (class "Default")
      (node (ref "IC1") (pin "4") (pinfunction "NC_4") (pintype "no_connect"))
    )
    (net (code "57") (name "unconnected-(IC4-NC-Pad4)") (class "Default")
      (node (ref "IC4") (pin "4") (pinfunction "NC_4") (pintype "no_connect"))
    )
    (net (code "58") (name "unconnected-(J1-Pad1)") (class "Default")
      (node (ref "J1") (pin "1") (pinfunction "1_1") (pintype "bidirectional"))
    )
    (net (code "59") (name "unconnected-(J1-Pad6)") (class "Default")
      (node (ref "J1") (pin "6") (pinfunction "6_6") (pintype "bidirectional"))
    )
    (net (code "60") (name "unconnected-(J1-Pad7)") (class "Default")
      (node (ref "J1") (pin "7") (pinfunction "7_7") (pintype "bidirectional"))
    )
    (net (code "61") (name "unconnected-(J2-PadA8)") (class "Default")
      (node (ref "J2") (pin "A8") (pinfunction "A8_A8") (pintype "bidirectional"))
    )
    (net (code "62") (name "unconnected-(J2-PadB8)") (class "Default")
      (node (ref "J2") (pin "B8") (pinfunction "B8_B8") (pintype "bidirectional"))
    )
    (net (code "63") (name "unconnected-(J4-DAT1-PadP8)") (class "Default")
      (node (ref "J4") (pin "P8") (pinfunction "DAT1_P8") (pintype "bidirectional"))
    )
    (net (code "64") (name "unconnected-(J4-DAT2-PadP1)") (class "Default")
      (node (ref "J4") (pin "P1") (pinfunction "DAT2_P1") (pintype "bidirectional"))
    )
    (net (code "65") (name "unconnected-(J4-DETECTION_1-PadS1)") (class "Default")
      (node (ref "J4") (pin "S1") (pinfunction "DETECTION_1_S1") (pintype "bidirectional"))
    )
    (net (code "66") (name "unconnected-(J4-DETECTION_2-PadS2)") (class "Default")
      (node (ref "J4") (pin "S2") (pinfunction "DETECTION_2_S2") (pintype "bidirectional"))
    )
    (net (code "67") (name "unconnected-(U2-NC-Pad22)") (class "Default")
      (node (ref "U2") (pin "22") (pinfunction "NC_22") (pintype "no_connect"))
    )
    (net (code "68") (name "unconnected-(U4-~{ALERT}-Pad5)") (class "Default")
      (node (ref "U4") (pin "5") (pinfunction "~{ALERT}_5") (pintype "output"))
    )
  )
)
